# knobby.net
KiCad netlist of a schematic drawn in EAGLE
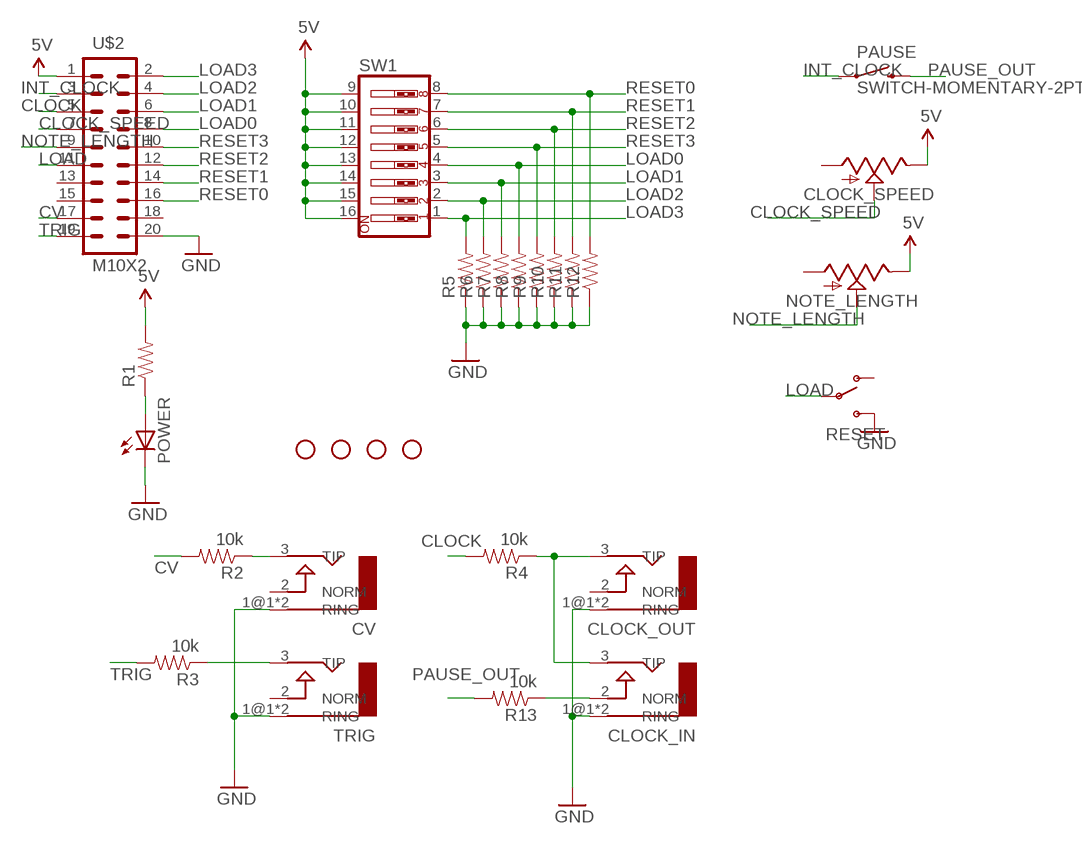
[diagram p0: schematic, sheet 1]

(export (version "E")
  (design (tool "Eeschema 10.0.6"))
  (components
    (comp (ref "CLOCK_IN")
      (value "AUDIO-JACKERTHENVAR")
      (footprint "eagle-import:ERTHENVAR-JACK")
      (libsource (lib "eagle-import") (part "AUDIO-JACKERTHENVAR"))
    )
    (comp (ref "CLOCK_OUT")
      (value "AUDIO-JACKERTHENVAR")
      (footprint "eagle-import:ERTHENVAR-JACK")
      (libsource (lib "eagle-import") (part "AUDIO-JACKERTHENVAR"))
    )
    (comp (ref "CLOCK_SPEED")
      (value "SPARKFUN_POTPDB12")
      (footprint "eagle-import:SPARKFUN_PDB12")
      (libsource (lib "eagle-import") (part "SPARKFUN_POTPDB12"))
    )
    (comp (ref "CV")
      (value "AUDIO-JACKERTHENVAR")
      (footprint "eagle-import:ERTHENVAR-JACK")
      (libsource (lib "eagle-import") (part "AUDIO-JACKERTHENVAR"))
    )
    (comp (ref "NOTE_LENGTH")
      (value "SPARKFUN_POTPDB12")
      (footprint "eagle-import:SPARKFUN_PDB12")
      (libsource (lib "eagle-import") (part "SPARKFUN_POTPDB12"))
    )
    (comp (ref "PAUSE")
      (value "SWITCH-MOMENTARY-2PTH")
      (footprint "eagle-import:TACTILE-PTH")
      (libsource (lib "eagle-import") (part "SWITCH-MOMENTARY-2PTH"))
    )
    (comp (ref "POWER")
      (value "LED3MM")
      (footprint "eagle-import:LED3MM")
      (libsource (lib "eagle-import") (part "LED3MM"))
    )
    (comp (ref "R1")
      (value "RESISTOR0603")
      (footprint "eagle-import:0603-RES")
      (libsource (lib "eagle-import") (part "RESISTOR0603"))
    )
    (comp (ref "R2")
      (value "10k")
      (footprint "eagle-import:0603-RES")
      (libsource (lib "eagle-import") (part "RESISTOR0603"))
    )
    (comp (ref "R3")
      (value "10k")
      (footprint "eagle-import:0603-RES")
      (libsource (lib "eagle-import") (part "RESISTOR0603"))
    )
    (comp (ref "R4")
      (value "10k")
      (footprint "eagle-import:0603-RES")
      (libsource (lib "eagle-import") (part "RESISTOR0603"))
    )
    (comp (ref "R5")
      (value "RESISTOR0603")
      (footprint "eagle-import:0603-RES")
      (libsource (lib "eagle-import") (part "RESISTOR0603"))
    )
    (comp (ref "R6")
      (value "RESISTOR0603")
      (footprint "eagle-import:0603-RES")
      (libsource (lib "eagle-import") (part "RESISTOR0603"))
    )
    (comp (ref "R7")
      (value "RESISTOR0603")
      (footprint "eagle-import:0603-RES")
      (libsource (lib "eagle-import") (part "RESISTOR0603"))
    )
    (comp (ref "R8")
      (value "RESISTOR0603")
      (footprint "eagle-import:0603-RES")
      (libsource (lib "eagle-import") (part "RESISTOR0603"))
    )
    (comp (ref "R9")
      (value "RESISTOR0603")
      (footprint "eagle-import:0603-RES")
      (libsource (lib "eagle-import") (part "RESISTOR0603"))
    )
    (comp (ref "R10")
      (value "RESISTOR0603")
      (footprint "eagle-import:0603-RES")
      (libsource (lib "eagle-import") (part "RESISTOR0603"))
    )
    (comp (ref "R11")
      (value "RESISTOR0603")
      (footprint "eagle-import:0603-RES")
      (libsource (lib "eagle-import") (part "RESISTOR0603"))
    )
    (comp (ref "R12")
      (value "RESISTOR0603")
      (footprint "eagle-import:0603-RES")
      (libsource (lib "eagle-import") (part "RESISTOR0603"))
    )
    (comp (ref "R13")
      (value "10k")
      (footprint "eagle-import:0603-RES")
      (libsource (lib "eagle-import") (part "RESISTOR0603"))
    )
    (comp (ref "RESET")
      (value "SWITCH-SPDTPTH")
      (footprint "eagle-import:SWITCH-SPDT")
      (libsource (lib "eagle-import") (part "SWITCH-SPDTPTH"))
    )
    (comp (ref "STANDOFF1")
      (value "STAND-OFF")
      (footprint "eagle-import:STAND-OFF")
      (libsource (lib "eagle-import") (part "STAND-OFF"))
    )
    (comp (ref "STANDOFF2")
      (value "STAND-OFF")
      (footprint "eagle-import:STAND-OFF")
      (libsource (lib "eagle-import") (part "STAND-OFF"))
    )
    (comp (ref "STANDOFF3")
      (value "STAND-OFF")
      (footprint "eagle-import:STAND-OFF")
      (libsource (lib "eagle-import") (part "STAND-OFF"))
    )
    (comp (ref "STANDOFF4")
      (value "STAND-OFF")
      (footprint "eagle-import:STAND-OFF")
      (libsource (lib "eagle-import") (part "STAND-OFF"))
    )
    (comp (ref "SW1")
      (value "SW_DIP-8")
      (footprint "eagle-import:DIPSWITCH-08")
      (libsource (lib "eagle-import") (part "SW_DIP-8"))
    )
    (comp (ref "TRIG")
      (value "AUDIO-JACKERTHENVAR")
      (footprint "eagle-import:ERTHENVAR-JACK")
      (libsource (lib "eagle-import") (part "AUDIO-JACKERTHENVAR"))
    )
    (comp (ref "U$2")
      (value "M10X2")
      (footprint "eagle-import:2X10")
      (libsource (lib "eagle-import") (part "M10X2"))
    )
  )
  (nets
    (net (code "1") (name "/CLOCK") (class "Default")
      (node (ref "R4") (pin "2") (pinfunction "2_2") (pintype "passive"))
      (node (ref "U$2") (pin "5") (pinfunction "5_5") (pintype "passive"))
    )
    (net (code "2") (name "/CLOCK_SPEED") (class "Default")
      (node (ref "CLOCK_SPEED") (pin "2") (pinfunction "S_2") (pintype "passive"))
      (node (ref "U$2") (pin "7") (pinfunction "7_7") (pintype "passive"))
    )
    (net (code "3") (name "/CV") (class "Default")
      (node (ref "R2") (pin "2") (pinfunction "2_2") (pintype "passive"))
      (node (ref "U$2") (pin "17") (pinfunction "17_17") (pintype "passive"))
    )
    (net (code "4") (name "/INT_CLOCK") (class "Default")
      (node (ref "PAUSE") (pin "1") (pinfunction "1_1") (pintype "passive"))
      (node (ref "U$2") (pin "3") (pinfunction "3_3") (pintype "passive"))
    )
    (net (code "5") (name "/LOAD") (class "Default")
      (node (ref "RESET") (pin "2") (pinfunction "P_2") (pintype "passive"))
      (node (ref "U$2") (pin "11") (pinfunction "11_11") (pintype "passive"))
    )
    (net (code "6") (name "/LOAD0") (class "Default")
      (node (ref "R8") (pin "2") (pinfunction "2_2") (pintype "passive"))
      (node (ref "SW1") (pin "4") (pinfunction "4_4") (pintype "passive"))
      (node (ref "U$2") (pin "8") (pinfunction "8_8") (pintype "passive"))
    )
    (net (code "7") (name "/LOAD1") (class "Default")
      (node (ref "R7") (pin "2") (pinfunction "2_2") (pintype "passive"))
      (node (ref "SW1") (pin "3") (pinfunction "3_3") (pintype "passive"))
      (node (ref "U$2") (pin "6") (pinfunction "6_6") (pintype "passive"))
    )
    (net (code "8") (name "/LOAD2") (class "Default")
      (node (ref "R6") (pin "2") (pinfunction "2_2") (pintype "passive"))
      (node (ref "SW1") (pin "2") (pinfunction "2_2") (pintype "passive"))
      (node (ref "U$2") (pin "4") (pinfunction "4_4") (pintype "passive"))
    )
    (net (code "9") (name "/LOAD3") (class "Default")
      (node (ref "R5") (pin "2") (pinfunction "2_2") (pintype "passive"))
      (node (ref "SW1") (pin "1") (pinfunction "1_1") (pintype "passive"))
      (node (ref "U$2") (pin "2") (pinfunction "2_2") (pintype "passive"))
    )
    (net (code "10") (name "/NOTE_LENGTH") (class "Default")
      (node (ref "NOTE_LENGTH") (pin "2") (pinfunction "S_2") (pintype "passive"))
      (node (ref "U$2") (pin "9") (pinfunction "9_9") (pintype "passive"))
    )
    (net (code "11") (name "/PAUSE_OUT") (class "Default")
      (node (ref "PAUSE") (pin "3") (pinfunction "2_3") (pintype "passive"))
      (node (ref "R13") (pin "2") (pinfunction "2_2") (pintype "passive"))
    )
    (net (code "12") (name "/RESET0") (class "Default")
      (node (ref "R12") (pin "2") (pinfunction "2_2") (pintype "passive"))
      (node (ref "SW1") (pin "8") (pinfunction "8_8") (pintype "passive"))
      (node (ref "U$2") (pin "16") (pinfunction "16_16") (pintype "passive"))
    )
    (net (code "13") (name "/RESET1") (class "Default")
      (node (ref "R11") (pin "2") (pinfunction "2_2") (pintype "passive"))
      (node (ref "SW1") (pin "7") (pinfunction "7_7") (pintype "passive"))
      (node (ref "U$2") (pin "14") (pinfunction "14_14") (pintype "passive"))
    )
    (net (code "14") (name "/RESET2") (class "Default")
      (node (ref "R10") (pin "2") (pinfunction "2_2") (pintype "passive"))
      (node (ref "SW1") (pin "6") (pinfunction "6_6") (pintype "passive"))
      (node (ref "U$2") (pin "12") (pinfunction "12_12") (pintype "passive"))
    )
    (net (code "15") (name "/RESET3") (class "Default")
      (node (ref "R9") (pin "2") (pinfunction "2_2") (pintype "passive"))
      (node (ref "SW1") (pin "5") (pinfunction "5_5") (pintype "passive"))
      (node (ref "U$2") (pin "10") (pinfunction "10_10") (pintype "passive"))
    )
    (net (code "16") (name "/TRIG") (class "Default")
      (node (ref "R3") (pin "2") (pinfunction "2_2") (pintype "passive"))
      (node (ref "U$2") (pin "19") (pinfunction "19_19") (pintype "passive"))
    )
    (net (code "17") (name "5V") (class "Default")
      (node (ref "CLOCK_SPEED") (pin "3") (pinfunction "E_3") (pintype "passive"))
      (node (ref "NOTE_LENGTH") (pin "3") (pinfunction "E_3") (pintype "passive"))
      (node (ref "R1") (pin "2") (pinfunction "2_2") (pintype "passive"))
      (node (ref "SW1") (pin "10") (pinfunction "10_10") (pintype "passive"))
      (node (ref "SW1") (pin "11") (pinfunction "11_11") (pintype "passive"))
      (node (ref "SW1") (pin "12") (pinfunction "12_12") (pintype "passive"))
      (node (ref "SW1") (pin "13") (pinfunction "13_13") (pintype "passive"))
      (node (ref "SW1") (pin "14") (pinfunction "14_14") (pintype "passive"))
      (node (ref "SW1") (pin "15") (pinfunction "15_15") (pintype "passive"))
      (node (ref "SW1") (pin "16") (pinfunction "16_16") (pintype "passive"))
      (node (ref "SW1") (pin "9") (pinfunction "9_9") (pintype "passive"))
      (node (ref "U$2") (pin "1") (pinfunction "1_1") (pintype "passive"))
    )
    (net (code "18") (name "GND") (class "Default")
      (node (ref "CLOCK_IN") (pin "1@1") (pinfunction "RING_1@1") (pintype "bidirectional"))
      (node (ref "CLOCK_IN") (pin "1@2") (pinfunction "RING_1@2") (pintype "bidirectional"))
      (node (ref "CLOCK_OUT") (pin "1@1") (pinfunction "RING_1@1") (pintype "bidirectional"))
      (node (ref "CLOCK_OUT") (pin "1@2") (pinfunction "RING_1@2") (pintype "bidirectional"))
      (node (ref "CV") (pin "1@1") (pinfunction "RING_1@1") (pintype "bidirectional"))
      (node (ref "CV") (pin "1@2") (pinfunction "RING_1@2") (pintype "bidirectional"))
      (node (ref "POWER") (pin "K") (pinfunction "C_K") (pintype "passive"))
      (node (ref "R10") (pin "1") (pinfunction "1_1") (pintype "passive"))
      (node (ref "R11") (pin "1") (pinfunction "1_1") (pintype "passive"))
      (node (ref "R12") (pin "1") (pinfunction "1_1") (pintype "passive"))
      (node (ref "R5") (pin "1") (pinfunction "1_1") (pintype "passive"))
      (node (ref "R6") (pin "1") (pinfunction "1_1") (pintype "passive"))
      (node (ref "R7") (pin "1") (pinfunction "1_1") (pintype "passive"))
      (node (ref "R8") (pin "1") (pinfunction "1_1") (pintype "passive"))
      (node (ref "R9") (pin "1") (pinfunction "1_1") (pintype "passive"))
      (node (ref "RESET") (pin "3") (pinfunction "S_3") (pintype "passive"))
      (node (ref "TRIG") (pin "1@1") (pinfunction "RING_1@1") (pintype "bidirectional"))
      (node (ref "TRIG") (pin "1@2") (pinfunction "RING_1@2") (pintype "bidirectional"))
      (node (ref "U$2") (pin "20") (pinfunction "20_20") (pintype "passive"))
    )
    (net (code "19") (name "Net-(CLOCK_IN-NORM)") (class "Default")
      (node (ref "CLOCK_IN") (pin "2") (pinfunction "NORM_2") (pintype "bidirectional"))
      (node (ref "R13") (pin "1") (pinfunction "1_1") (pintype "passive"))
    )
    (net (code "20") (name "Net-(CLOCK_IN-TIP)") (class "Default")
      (node (ref "CLOCK_IN") (pin "3") (pinfunction "TIP_3") (pintype "bidirectional"))
      (node (ref "CLOCK_OUT") (pin "3") (pinfunction "TIP_3") (pintype "bidirectional"))
      (node (ref "R4") (pin "1") (pinfunction "1_1") (pintype "passive"))
    )
    (net (code "21") (name "Net-(CV-TIP)") (class "Default")
      (node (ref "CV") (pin "3") (pinfunction "TIP_3") (pintype "bidirectional"))
      (node (ref "R2") (pin "1") (pinfunction "1_1") (pintype "passive"))
    )
    (net (code "22") (name "Net-(POWER-PadA)") (class "Default")
      (node (ref "POWER") (pin "A") (pinfunction "A_A") (pintype "passive"))
      (node (ref "R1") (pin "1") (pinfunction "1_1") (pintype "passive"))
    )
    (net (code "23") (name "Net-(TRIG-TIP)") (class "Default")
      (node (ref "R3") (pin "1") (pinfunction "1_1") (pintype "passive"))
      (node (ref "TRIG") (pin "3") (pinfunction "TIP_3") (pintype "bidirectional"))
    )
    (net (code "24") (name "unconnected-(CLOCK_OUT-NORM-Pad2)") (class "Default")
      (node (ref "CLOCK_OUT") (pin "2") (pinfunction "NORM_2") (pintype "bidirectional"))
    )
    (net (code "25") (name "unconnected-(CLOCK_SPEED-A-Pad1)") (class "Default")
      (node (ref "CLOCK_SPEED") (pin "1") (pinfunction "A_1") (pintype "passive"))
    )
    (net (code "26") (name "unconnected-(CV-NORM-Pad2)") (class "Default")
      (node (ref "CV") (pin "2") (pinfunction "NORM_2") (pintype "bidirectional"))
    )
    (net (code "27") (name "unconnected-(NOTE_LENGTH-A-Pad1)") (class "Default")
      (node (ref "NOTE_LENGTH") (pin "1") (pinfunction "A_1") (pintype "passive"))
    )
    (net (code "28") (name "unconnected-(RESET-O-Pad1)") (class "Default")
      (node (ref "RESET") (pin "1") (pinfunction "O_1") (pintype "passive"))
    )
    (net (code "29") (name "unconnected-(TRIG-NORM-Pad2)") (class "Default")
      (node (ref "TRIG") (pin "2") (pinfunction "NORM_2") (pintype "bidirectional"))
    )
    (net (code "30") (name "unconnected-(U$2-Pad13)") (class "Default")
      (node (ref "U$2") (pin "13") (pinfunction "13_13") (pintype "passive"))
    )
    (net (code "31") (name "unconnected-(U$2-Pad15)") (class "Default")
      (node (ref "U$2") (pin "15") (pinfunction "15_15") (pintype "passive"))
    )
    (net (code "32") (name "unconnected-(U$2-Pad18)") (class "Default")
      (node (ref "U$2") (pin "18") (pinfunction "18_18") (pintype "passive"))
    )
  )
)
